# nRF7002-DK.net
KiCad netlist of a schematic drawn in Altium Designer
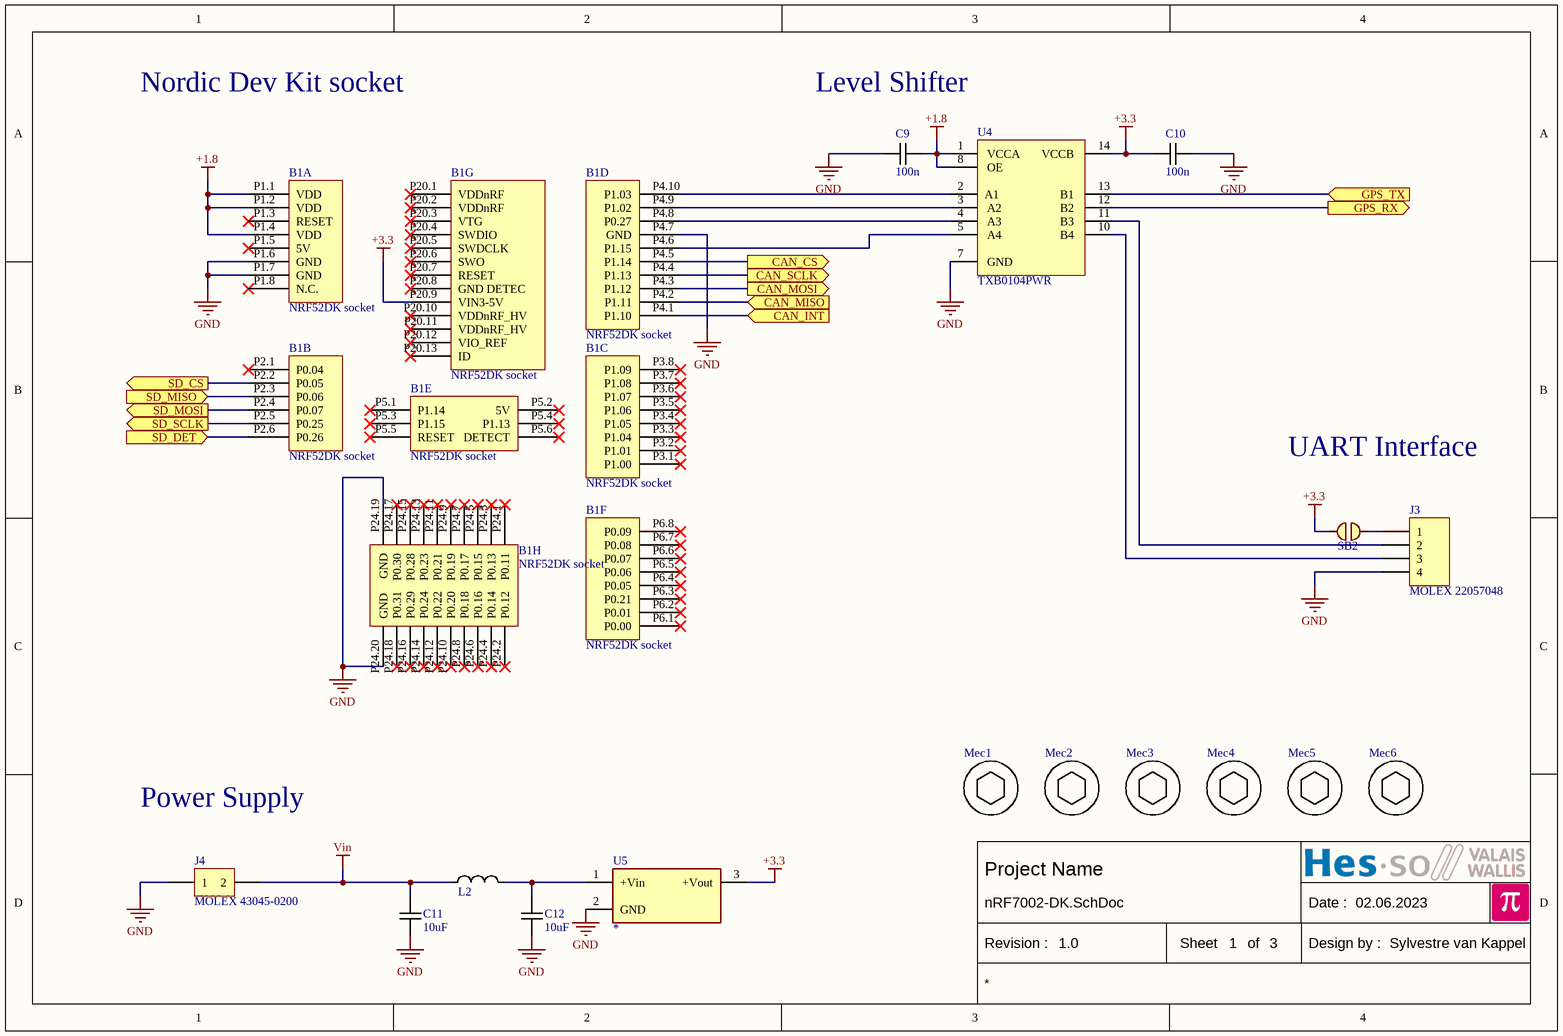
[diagram p0: nRF7002-DK.SchDoc]

(export (version "E")
  (design (tool "Eeschema 10.0.6"))
  (components
    (comp (ref "B1")
      (value "NRF52DK socket")
      (footprint "nRF5340DK SOCKET")
      (description "nRF53 development kit")
      (libsource (lib "DevBoard") (part "nRF5340DK Socket"))
    )
    (comp (ref "C9")
      (value "100n")
      (footprint "CAPACITOR 1608 REFLOW")
      (description "Capacitor")
      (libsource (lib "Capacitor") (part "Capacitor"))
    )
    (comp (ref "C10")
      (value "100n")
      (footprint "CAPACITOR 1608 REFLOW")
      (description "Capacitor")
      (libsource (lib "Capacitor") (part "Capacitor"))
    )
    (comp (ref "C11")
      (value "10uF")
      (footprint "CAPACITOR 3216 REFLOW")
      (description "Capacitor")
      (libsource (lib "Capacitor") (part "Capacitor"))
    )
    (comp (ref "C12")
      (value "10uF")
      (footprint "CAPACITOR 3216 REFLOW")
      (description "Capacitor")
      (libsource (lib "Capacitor") (part "Capacitor"))
    )
    (comp (ref "J3")
      (value "MOLEX 22057048")
      (footprint "MOLEX 22057048")
      (description "KK 254 Wire-to-Board Header, Right-Angle, 4 Circuits")
      (libsource (lib "Connector") (part "MOLEX 22057048"))
    )
    (comp (ref "J4")
      (value "MOLEX 43045-0200")
      (footprint "MOLEX 43045-0200")
      (description "Micro-Fit 3.0 Right-Angle Header, 3.00mm, Dual Row, 2 Circuits")
      (libsource (lib "Connector") (part "MOLEX 43045-0200"))
    )
    (comp (ref "L2")
      (value "*")
      (footprint "TCK141")
      (description "Inductor")
      (libsource (lib "Inductor") (part "Inductor"))
    )
    (comp (ref "Mec1")
      (value "~")
      (footprint "Screw Hex Socket M3X5 Unconnected")
      (description "Screw Hex Socket Unconnected BN610")
      (libsource (lib "Mechanic") (part "Screw Hex Socket Unconnected"))
    )
    (comp (ref "Mec2")
      (value "~")
      (footprint "Screw Hex Socket M3X5 Unconnected")
      (description "Screw Hex Socket Unconnected BN610")
      (libsource (lib "Mechanic") (part "Screw Hex Socket Unconnected"))
    )
    (comp (ref "Mec3")
      (value "~")
      (footprint "Screw Hex Socket M3X5 Unconnected")
      (description "Screw Hex Socket Unconnected BN610")
      (libsource (lib "Mechanic") (part "Screw Hex Socket Unconnected"))
    )
    (comp (ref "Mec4")
      (value "~")
      (footprint "Screw Hex Socket M3X5 Unconnected")
      (description "Screw Hex Socket Unconnected BN610")
      (libsource (lib "Mechanic") (part "Screw Hex Socket Unconnected"))
    )
    (comp (ref "Mec5")
      (value "~")
      (footprint "Screw Hex Socket M3X5 Unconnected")
      (description "Screw Hex Socket Unconnected BN610")
      (libsource (lib "Mechanic") (part "Screw Hex Socket Unconnected"))
    )
    (comp (ref "Mec6")
      (value "~")
      (footprint "Screw Hex Socket M3X5 Unconnected")
      (description "Screw Hex Socket Unconnected BN610")
      (libsource (lib "Mechanic") (part "Screw Hex Socket Unconnected"))
    )
    (comp (ref "SB2")
      (value "*")
      (footprint "Solder Bridge 1mm Unconnected")
      (description "Solderbridge Unconnected")
      (libsource (lib "Jumper") (part "Solderbridge Unconnected"))
    )
    (comp (ref "U4")
      (value "TXB0104PWR")
      (footprint "TSSOP14 P0.65 C4.4x5.0 H1.1")
      (libsource (lib "IntegratedCircuit") (part "TXB0104PWR"))
    )
    (comp (ref "U5")
      (value "*")
      (footprint "TRACO TSR 1")
      (description "DC/DC Converter")
      (libsource (lib "VoltageConverter") (part "TRACO TSR 1"))
    )
  )
  (nets
    (net (code "1") (name "+1.8") (class "Default")
      (node (ref "B1") (pin "P1.1") (pinfunction "VDD_P1.1") (pintype "passive"))
      (node (ref "B1") (pin "P1.2") (pinfunction "VDD_P1.2") (pintype "passive"))
      (node (ref "B1") (pin "P1.4") (pinfunction "VDD_P1.4") (pintype "passive"))
      (node (ref "C9") (pin "1") (pinfunction "1_1") (pintype "passive"))
      (node (ref "U4") (pin "1") (pinfunction "VCCA_1") (pintype "passive"))
      (node (ref "U4") (pin "8") (pinfunction "OE_8") (pintype "passive"))
    )
    (net (code "2") (name "+3.3") (class "Default")
      (node (ref "B1") (pin "P20.9") (pinfunction "VIN3-5V_P20.9") (pintype "passive"))
      (node (ref "C10") (pin "2") (pinfunction "2_2") (pintype "passive"))
      (node (ref "SB2") (pin "2") (pinfunction "1_2") (pintype "passive"))
      (node (ref "U4") (pin "14") (pinfunction "VCCB_14") (pintype "passive"))
      (node (ref "U5") (pin "3") (pinfunction "+Vout_3") (pintype "passive"))
    )
    (net (code "3") (name "/CAN_CS") (class "Default")
      (node (ref "B1") (pin "P4.5") (pinfunction "P1.14_P4.5") (pintype "passive"))
    )
    (net (code "4") (name "/CAN_INT") (class "Default")
      (node (ref "B1") (pin "P4.1") (pinfunction "P1.10_P4.1") (pintype "passive"))
    )
    (net (code "5") (name "/CAN_MISO") (class "Default")
      (node (ref "B1") (pin "P4.2") (pinfunction "P1.11_P4.2") (pintype "passive"))
    )
    (net (code "6") (name "/CAN_MOSI") (class "Default")
      (node (ref "B1") (pin "P4.3") (pinfunction "P1.12_P4.3") (pintype "passive"))
    )
    (net (code "7") (name "/CAN_SCLK") (class "Default")
      (node (ref "B1") (pin "P4.4") (pinfunction "P1.13_P4.4") (pintype "passive"))
    )
    (net (code "8") (name "/GPS_RX") (class "Default")
      (node (ref "U4") (pin "12") (pinfunction "B2_12") (pintype "passive"))
    )
    (net (code "9") (name "/GPS_TX") (class "Default")
      (node (ref "U4") (pin "13") (pinfunction "B1_13") (pintype "passive"))
    )
    (net (code "10") (name "/SD_CS") (class "Default")
      (node (ref "B1") (pin "P2.2") (pinfunction "P0.05_P2.2") (pintype "passive"))
    )
    (net (code "11") (name "/SD_DET") (class "Default")
      (node (ref "B1") (pin "P2.6") (pinfunction "P0.26_P2.6") (pintype "passive"))
    )
    (net (code "12") (name "/SD_MISO") (class "Default")
      (node (ref "B1") (pin "P2.3") (pinfunction "P0.06_P2.3") (pintype "passive"))
    )
    (net (code "13") (name "/SD_MOSI") (class "Default")
      (node (ref "B1") (pin "P2.4") (pinfunction "P0.07_P2.4") (pintype "passive"))
    )
    (net (code "14") (name "/SD_SCLK") (class "Default")
      (node (ref "B1") (pin "P2.5") (pinfunction "P0.25_P2.5") (pintype "passive"))
    )
    (net (code "15") (name "GND") (class "Default")
      (node (ref "B1") (pin "P1.6") (pinfunction "GND_P1.6") (pintype "passive"))
      (node (ref "B1") (pin "P1.7") (pinfunction "GND_P1.7") (pintype "passive"))
      (node (ref "B1") (pin "P24.19") (pinfunction "GND_P24.19") (pintype "passive"))
      (node (ref "B1") (pin "P24.20") (pinfunction "GND_P24.20") (pintype "passive"))
      (node (ref "B1") (pin "P4.7") (pinfunction "GND_P4.7") (pintype "passive"))
      (node (ref "C10") (pin "1") (pinfunction "1_1") (pintype "passive"))
      (node (ref "C11") (pin "2") (pinfunction "2_2") (pintype "passive"))
      (node (ref "C12") (pin "2") (pinfunction "2_2") (pintype "passive"))
      (node (ref "C9") (pin "2") (pinfunction "2_2") (pintype "passive"))
      (node (ref "J3") (pin "4") (pinfunction "4_4") (pintype "passive"))
      (node (ref "J4") (pin "1") (pinfunction "1_1") (pintype "passive"))
      (node (ref "U4") (pin "7") (pinfunction "GND_7") (pintype "passive"))
      (node (ref "U5") (pin "2") (pinfunction "GND_2") (pintype "passive"))
    )
    (net (code "16") (name "Net-(B1D-P0.27)") (class "Default")
      (node (ref "B1") (pin "P4.8") (pinfunction "P0.27_P4.8") (pintype "passive"))
      (node (ref "U4") (pin "4") (pinfunction "A3_4") (pintype "passive"))
    )
    (net (code "17") (name "Net-(B1D-P1.02)") (class "Default")
      (node (ref "B1") (pin "P4.9") (pinfunction "P1.02_P4.9") (pintype "passive"))
      (node (ref "U4") (pin "3") (pinfunction "A2_3") (pintype "passive"))
    )
    (net (code "18") (name "Net-(B1D-P1.03)") (class "Default")
      (node (ref "B1") (pin "P4.10") (pinfunction "P1.03_P4.10") (pintype "passive"))
      (node (ref "U4") (pin "2") (pinfunction "A1_2") (pintype "passive"))
    )
    (net (code "19") (name "Net-(B1D-P1.15)") (class "Default")
      (node (ref "B1") (pin "P4.6") (pinfunction "P1.15_P4.6") (pintype "passive"))
      (node (ref "U4") (pin "5") (pinfunction "A4_5") (pintype "passive"))
    )
    (net (code "20") (name "Net-(SB2-0)") (class "Default")
      (node (ref "J3") (pin "1") (pinfunction "1_1") (pintype "passive"))
      (node (ref "SB2") (pin "1") (pinfunction "0_1") (pintype "passive"))
    )
    (net (code "21") (name "Net-(U4-B3)") (class "Default")
      (node (ref "J3") (pin "2") (pinfunction "2_2") (pintype "passive"))
      (node (ref "U4") (pin "11") (pinfunction "B3_11") (pintype "passive"))
    )
    (net (code "22") (name "Net-(U4-B4)") (class "Default")
      (node (ref "J3") (pin "3") (pinfunction "3_3") (pintype "passive"))
      (node (ref "U4") (pin "10") (pinfunction "B4_10") (pintype "passive"))
    )
    (net (code "23") (name "Net-(U5-+Vin)") (class "Default")
      (node (ref "C12") (pin "1") (pinfunction "1_1") (pintype "passive"))
      (node (ref "L2") (pin "2") (pinfunction "2_2") (pintype "passive"))
      (node (ref "U5") (pin "1") (pinfunction "+Vin_1") (pintype "passive"))
    )
    (net (code "24") (name "Vin") (class "Default")
      (node (ref "C11") (pin "1") (pinfunction "1_1") (pintype "passive"))
      (node (ref "J4") (pin "2") (pinfunction "2_2") (pintype "passive"))
      (node (ref "L2") (pin "1") (pinfunction "1_1") (pintype "passive"))
    )
    (net (code "25") (name "unconnected-(B1A-5V-PadP1.5)") (class "Default")
      (node (ref "B1") (pin "P1.5") (pinfunction "5V_P1.5") (pintype "passive+no_connect"))
    )
    (net (code "26") (name "unconnected-(B1A-N.C.-PadP1.8)") (class "Default")
      (node (ref "B1") (pin "P1.8") (pinfunction "N.C._P1.8") (pintype "passive+no_connect"))
    )
    (net (code "27") (name "unconnected-(B1A-RESET-PadP1.3)") (class "Default")
      (node (ref "B1") (pin "P1.3") (pinfunction "RESET_P1.3") (pintype "passive+no_connect"))
    )
    (net (code "28") (name "unconnected-(B1B-P0.04-PadP2.1)") (class "Default")
      (node (ref "B1") (pin "P2.1") (pinfunction "P0.04_P2.1") (pintype "passive+no_connect"))
    )
    (net (code "29") (name "unconnected-(B1C-P1.00-PadP3.1)") (class "Default")
      (node (ref "B1") (pin "P3.1") (pinfunction "P1.00_P3.1") (pintype "passive+no_connect"))
    )
    (net (code "30") (name "unconnected-(B1C-P1.01-PadP3.2)") (class "Default")
      (node (ref "B1") (pin "P3.2") (pinfunction "P1.01_P3.2") (pintype "passive+no_connect"))
    )
    (net (code "31") (name "unconnected-(B1C-P1.04-PadP3.3)") (class "Default")
      (node (ref "B1") (pin "P3.3") (pinfunction "P1.04_P3.3") (pintype "passive+no_connect"))
    )
    (net (code "32") (name "unconnected-(B1C-P1.05-PadP3.4)") (class "Default")
      (node (ref "B1") (pin "P3.4") (pinfunction "P1.05_P3.4") (pintype "passive+no_connect"))
    )
    (net (code "33") (name "unconnected-(B1C-P1.06-PadP3.5)") (class "Default")
      (node (ref "B1") (pin "P3.5") (pinfunction "P1.06_P3.5") (pintype "passive+no_connect"))
    )
    (net (code "34") (name "unconnected-(B1C-P1.07-PadP3.6)") (class "Default")
      (node (ref "B1") (pin "P3.6") (pinfunction "P1.07_P3.6") (pintype "passive+no_connect"))
    )
    (net (code "35") (name "unconnected-(B1C-P1.08-PadP3.7)") (class "Default")
      (node (ref "B1") (pin "P3.7") (pinfunction "P1.08_P3.7") (pintype "passive+no_connect"))
    )
    (net (code "36") (name "unconnected-(B1C-P1.09-PadP3.8)") (class "Default")
      (node (ref "B1") (pin "P3.8") (pinfunction "P1.09_P3.8") (pintype "passive+no_connect"))
    )
    (net (code "37") (name "unconnected-(B1E-5V-PadP5.2)") (class "Default")
      (node (ref "B1") (pin "P5.2") (pinfunction "5V_P5.2") (pintype "passive+no_connect"))
    )
    (net (code "38") (name "unconnected-(B1E-DETECT-PadP5.6)") (class "Default")
      (node (ref "B1") (pin "P5.6") (pinfunction "DETECT_P5.6") (pintype "passive+no_connect"))
    )
    (net (code "39") (name "unconnected-(B1E-P1.13-PadP5.4)") (class "Default")
      (node (ref "B1") (pin "P5.4") (pinfunction "P1.13_P5.4") (pintype "passive+no_connect"))
    )
    (net (code "40") (name "unconnected-(B1E-P1.14-PadP5.1)") (class "Default")
      (node (ref "B1") (pin "P5.1") (pinfunction "P1.14_P5.1") (pintype "passive+no_connect"))
    )
    (net (code "41") (name "unconnected-(B1E-P1.15-PadP5.3)") (class "Default")
      (node (ref "B1") (pin "P5.3") (pinfunction "P1.15_P5.3") (pintype "passive+no_connect"))
    )
    (net (code "42") (name "unconnected-(B1E-RESET-PadP5.5)") (class "Default")
      (node (ref "B1") (pin "P5.5") (pinfunction "RESET_P5.5") (pintype "passive+no_connect"))
    )
    (net (code "43") (name "unconnected-(B1F-P0.00-PadP6.1)") (class "Default")
      (node (ref "B1") (pin "P6.1") (pinfunction "P0.00_P6.1") (pintype "passive+no_connect"))
    )
    (net (code "44") (name "unconnected-(B1F-P0.01-PadP6.2)") (class "Default")
      (node (ref "B1") (pin "P6.2") (pinfunction "P0.01_P6.2") (pintype "passive+no_connect"))
    )
    (net (code "45") (name "unconnected-(B1F-P0.05-PadP6.4)") (class "Default")
      (node (ref "B1") (pin "P6.4") (pinfunction "P0.05_P6.4") (pintype "passive+no_connect"))
    )
    (net (code "46") (name "unconnected-(B1F-P0.06-PadP6.5)") (class "Default")
      (node (ref "B1") (pin "P6.5") (pinfunction "P0.06_P6.5") (pintype "passive+no_connect"))
    )
    (net (code "47") (name "unconnected-(B1F-P0.07-PadP6.6)") (class "Default")
      (node (ref "B1") (pin "P6.6") (pinfunction "P0.07_P6.6") (pintype "passive+no_connect"))
    )
    (net (code "48") (name "unconnected-(B1F-P0.08-PadP6.7)") (class "Default")
      (node (ref "B1") (pin "P6.7") (pinfunction "P0.08_P6.7") (pintype "passive+no_connect"))
    )
    (net (code "49") (name "unconnected-(B1F-P0.09-PadP6.8)") (class "Default")
      (node (ref "B1") (pin "P6.8") (pinfunction "P0.09_P6.8") (pintype "passive+no_connect"))
    )
    (net (code "50") (name "unconnected-(B1F-P0.21-PadP6.3)") (class "Default")
      (node (ref "B1") (pin "P6.3") (pinfunction "P0.21_P6.3") (pintype "passive+no_connect"))
    )
    (net (code "51") (name "unconnected-(B1G-GND_DETEC-PadP20.8)") (class "Default")
      (node (ref "B1") (pin "P20.8") (pinfunction "GND_DETEC_P20.8") (pintype "passive+no_connect"))
    )
    (net (code "52") (name "unconnected-(B1G-ID-PadP20.13)") (class "Default")
      (node (ref "B1") (pin "P20.13") (pinfunction "ID_P20.13") (pintype "passive+no_connect"))
    )
    (net (code "53") (name "unconnected-(B1G-RESET-PadP20.7)") (class "Default")
      (node (ref "B1") (pin "P20.7") (pinfunction "RESET_P20.7") (pintype "passive+no_connect"))
    )
    (net (code "54") (name "unconnected-(B1G-SWDCLK-PadP20.5)") (class "Default")
      (node (ref "B1") (pin "P20.5") (pinfunction "SWDCLK_P20.5") (pintype "passive+no_connect"))
    )
    (net (code "55") (name "unconnected-(B1G-SWDIO-PadP20.4)") (class "Default")
      (node (ref "B1") (pin "P20.4") (pinfunction "SWDIO_P20.4") (pintype "passive+no_connect"))
    )
    (net (code "56") (name "unconnected-(B1G-SWO-PadP20.6)") (class "Default")
      (node (ref "B1") (pin "P20.6") (pinfunction "SWO_P20.6") (pintype "passive+no_connect"))
    )
    (net (code "57") (name "unconnected-(B1G-VDDnRF-PadP20.1)") (class "Default")
      (node (ref "B1") (pin "P20.1") (pinfunction "VDDnRF_P20.1") (pintype "passive+no_connect"))
    )
    (net (code "58") (name "unconnected-(B1G-VDDnRF-PadP20.2)") (class "Default")
      (node (ref "B1") (pin "P20.2") (pinfunction "VDDnRF_P20.2") (pintype "passive+no_connect"))
    )
    (net (code "59") (name "unconnected-(B1G-VDDnRF_HV-PadP20.10)") (class "Default")
      (node (ref "B1") (pin "P20.10") (pinfunction "VDDnRF_HV_P20.10") (pintype "passive+no_connect"))
    )
    (net (code "60") (name "unconnected-(B1G-VDDnRF_HV-PadP20.11)") (class "Default")
      (node (ref "B1") (pin "P20.11") (pinfunction "VDDnRF_HV_P20.11") (pintype "passive+no_connect"))
    )
    (net (code "61") (name "unconnected-(B1G-VIO_REF-PadP20.12)") (class "Default")
      (node (ref "B1") (pin "P20.12") (pinfunction "VIO_REF_P20.12") (pintype "passive+no_connect"))
    )
    (net (code "62") (name "unconnected-(B1G-VTG-PadP20.3)") (class "Default")
      (node (ref "B1") (pin "P20.3") (pinfunction "VTG_P20.3") (pintype "passive+no_connect"))
    )
    (net (code "63") (name "unconnected-(B1H-P0.11-PadP24.1)") (class "Default")
      (node (ref "B1") (pin "P24.1") (pinfunction "P0.11_P24.1") (pintype "passive+no_connect"))
    )
    (net (code "64") (name "unconnected-(B1H-P0.12-PadP24.2)") (class "Default")
      (node (ref "B1") (pin "P24.2") (pinfunction "P0.12_P24.2") (pintype "passive+no_connect"))
    )
    (net (code "65") (name "unconnected-(B1H-P0.13-PadP24.3)") (class "Default")
      (node (ref "B1") (pin "P24.3") (pinfunction "P0.13_P24.3") (pintype "passive+no_connect"))
    )
    (net (code "66") (name "unconnected-(B1H-P0.14-PadP24.4)") (class "Default")
      (node (ref "B1") (pin "P24.4") (pinfunction "P0.14_P24.4") (pintype "passive+no_connect"))
    )
    (net (code "67") (name "unconnected-(B1H-P0.15-PadP24.5)") (class "Default")
      (node (ref "B1") (pin "P24.5") (pinfunction "P0.15_P24.5") (pintype "passive+no_connect"))
    )
    (net (code "68") (name "unconnected-(B1H-P0.16-PadP24.6)") (class "Default")
      (node (ref "B1") (pin "P24.6") (pinfunction "P0.16_P24.6") (pintype "passive+no_connect"))
    )
    (net (code "69") (name "unconnected-(B1H-P0.17-PadP24.7)") (class "Default")
      (node (ref "B1") (pin "P24.7") (pinfunction "P0.17_P24.7") (pintype "passive+no_connect"))
    )
    (net (code "70") (name "unconnected-(B1H-P0.18-PadP24.8)") (class "Default")
      (node (ref "B1") (pin "P24.8") (pinfunction "P0.18_P24.8") (pintype "passive+no_connect"))
    )
    (net (code "71") (name "unconnected-(B1H-P0.19-PadP24.9)") (class "Default")
      (node (ref "B1") (pin "P24.9") (pinfunction "P0.19_P24.9") (pintype "passive+no_connect"))
    )
    (net (code "72") (name "unconnected-(B1H-P0.20-PadP24.10)") (class "Default")
      (node (ref "B1") (pin "P24.10") (pinfunction "P0.20_P24.10") (pintype "passive+no_connect"))
    )
    (net (code "73") (name "unconnected-(B1H-P0.21-PadP24.11)") (class "Default")
      (node (ref "B1") (pin "P24.11") (pinfunction "P0.21_P24.11") (pintype "passive+no_connect"))
    )
    (net (code "74") (name "unconnected-(B1H-P0.22-PadP24.12)") (class "Default")
      (node (ref "B1") (pin "P24.12") (pinfunction "P0.22_P24.12") (pintype "passive+no_connect"))
    )
    (net (code "75") (name "unconnected-(B1H-P0.23-PadP24.13)") (class "Default")
      (node (ref "B1") (pin "P24.13") (pinfunction "P0.23_P24.13") (pintype "passive+no_connect"))
    )
    (net (code "76") (name "unconnected-(B1H-P0.24-PadP24.14)") (class "Default")
      (node (ref "B1") (pin "P24.14") (pinfunction "P0.24_P24.14") (pintype "passive+no_connect"))
    )
    (net (code "77") (name "unconnected-(B1H-P0.28-PadP24.15)") (class "Default")
      (node (ref "B1") (pin "P24.15") (pinfunction "P0.28_P24.15") (pintype "passive+no_connect"))
    )
    (net (code "78") (name "unconnected-(B1H-P0.29-PadP24.16)") (class "Default")
      (node (ref "B1") (pin "P24.16") (pinfunction "P0.29_P24.16") (pintype "passive+no_connect"))
    )
    (net (code "79") (name "unconnected-(B1H-P0.30-PadP24.17)") (class "Default")
      (node (ref "B1") (pin "P24.17") (pinfunction "P0.30_P24.17") (pintype "passive+no_connect"))
    )
    (net (code "80") (name "unconnected-(B1H-P0.31-PadP24.18)") (class "Default")
      (node (ref "B1") (pin "P24.18") (pinfunction "P0.31_P24.18") (pintype "passive+no_connect"))
    )
  )
)
